# preamp.net
KiCad netlist of a schematic drawn in EAGLE
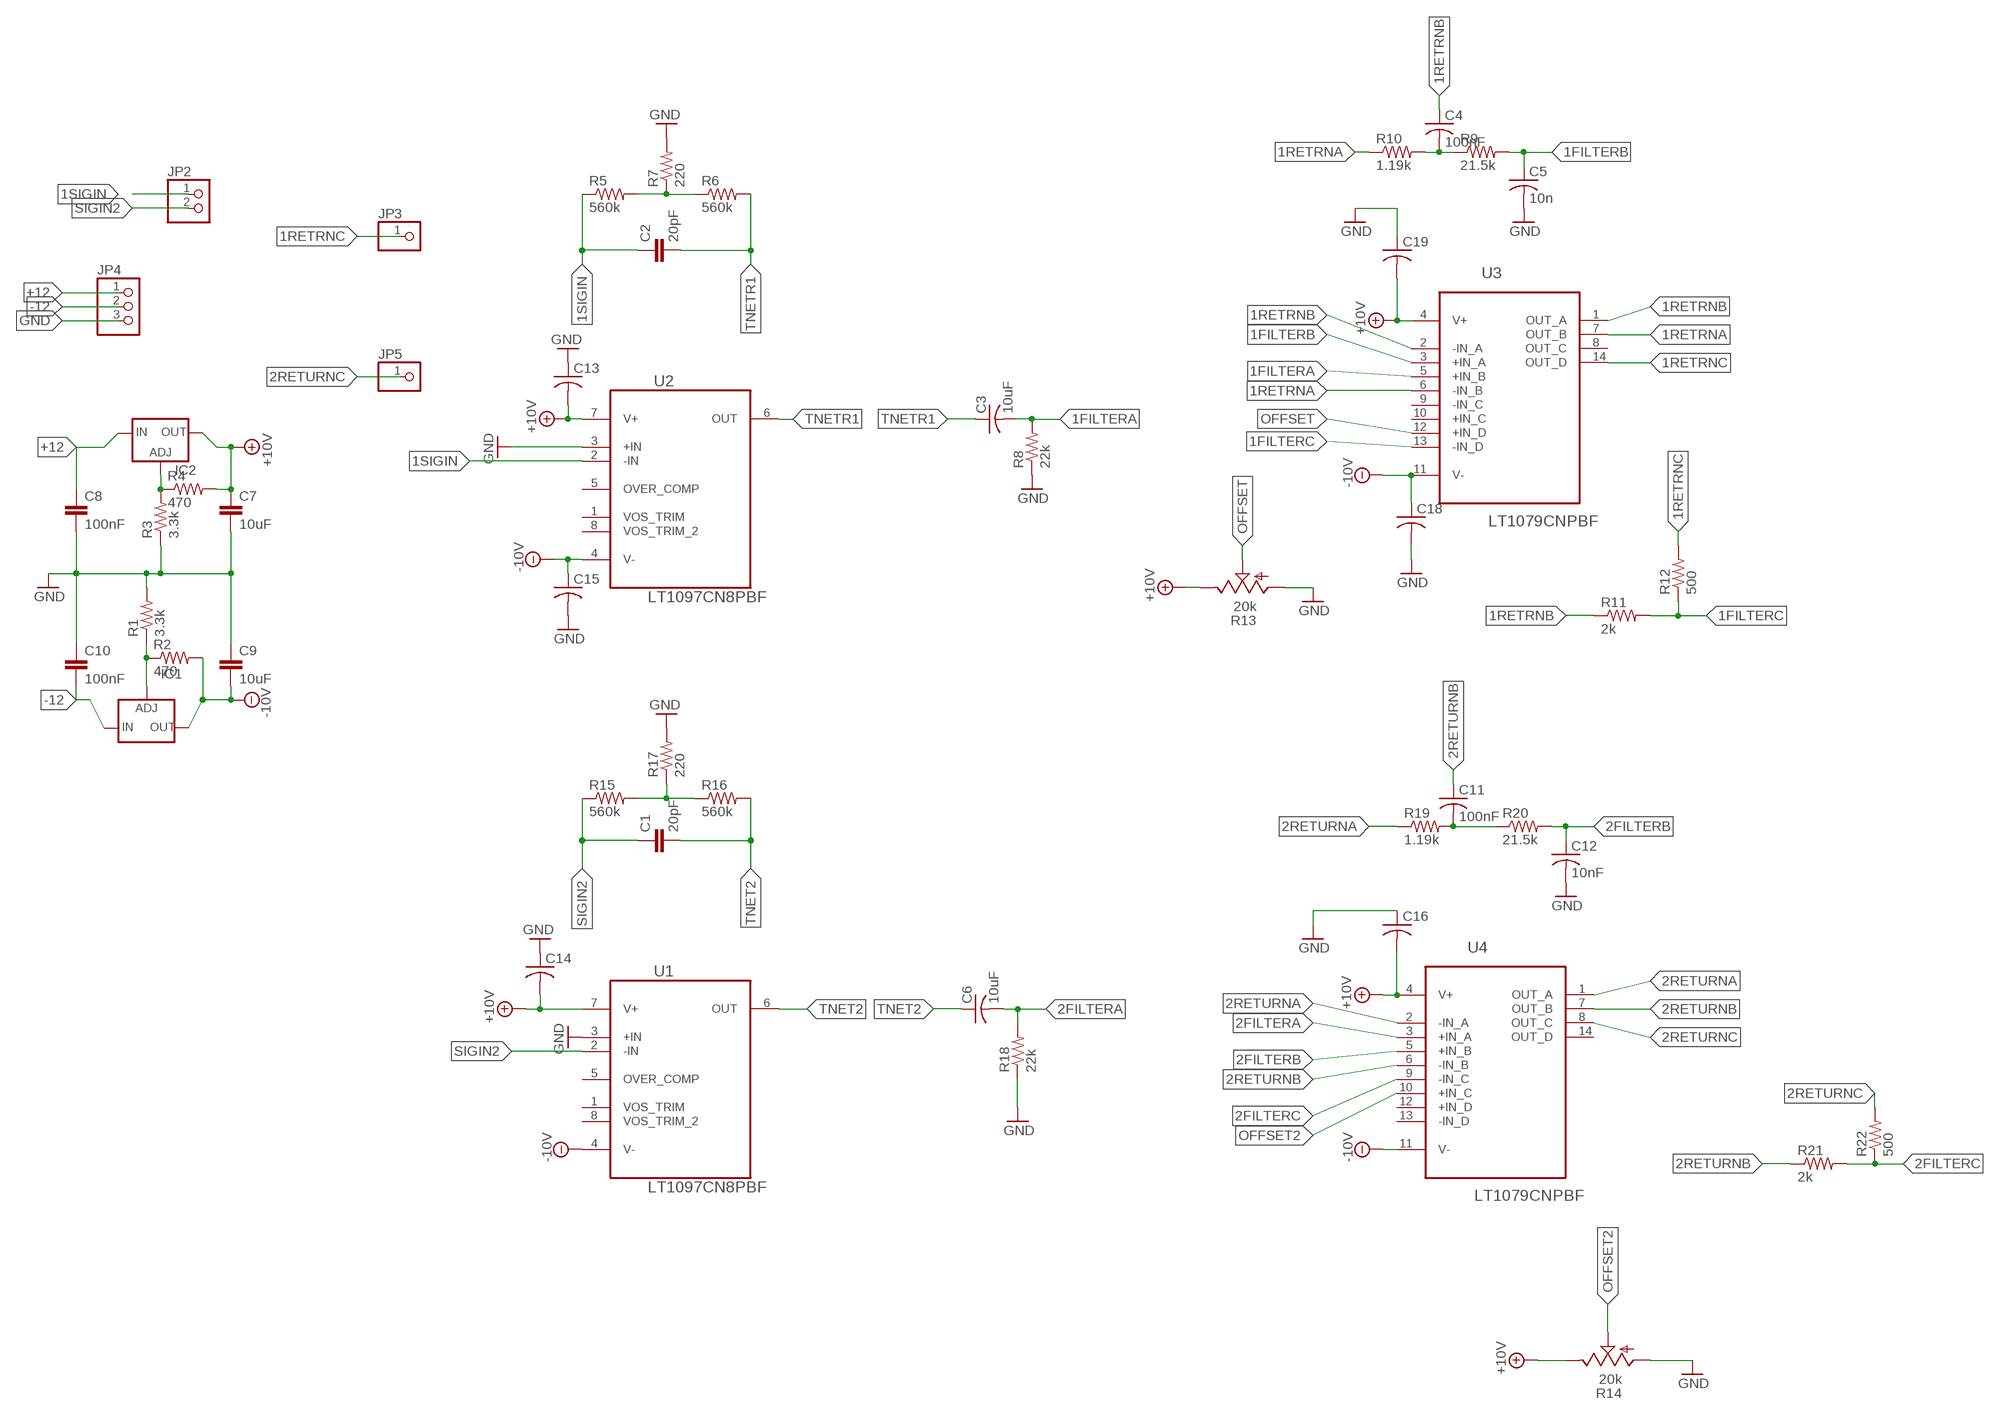
[diagram p0: schematic, sheet 1]

(export (version "E")
  (design (tool "Eeschema 10.0.6"))
  (components
    (comp (ref "C1")
      (value "20pF")
      (footprint "eagle-import:C025-030X050")
      (libsource (lib "eagle-import") (part "C-EU025-030X050"))
    )
    (comp (ref "C2")
      (value "20pF")
      (footprint "eagle-import:C025-030X050")
      (libsource (lib "eagle-import") (part "C-EU025-030X050"))
    )
    (comp (ref "C3")
      (value "10uF")
      (footprint "eagle-import:C050-030X075")
      (libsource (lib "eagle-import") (part "resistor_C-US050-030X075"))
    )
    (comp (ref "C4")
      (value "100nF")
      (footprint "eagle-import:C050-024X044")
      (libsource (lib "eagle-import") (part "resistor_C-US050-024X044"))
    )
    (comp (ref "C5")
      (value "10n")
      (footprint "eagle-import:C025-024X044")
      (libsource (lib "eagle-import") (part "resistor_C-US025-024X044"))
    )
    (comp (ref "C6")
      (value "10uF")
      (footprint "eagle-import:C050-030X075")
      (libsource (lib "eagle-import") (part "resistor_C-US050-030X075"))
    )
    (comp (ref "C7")
      (value "10uF")
      (footprint "eagle-import:C025-025X050")
      (libsource (lib "eagle-import") (part "C-EU025-025X050"))
    )
    (comp (ref "C8")
      (value "100nF")
      (footprint "eagle-import:C025-025X050")
      (libsource (lib "eagle-import") (part "C-EU025-025X050"))
    )
    (comp (ref "C9")
      (value "10uF")
      (footprint "eagle-import:C025-025X050")
      (libsource (lib "eagle-import") (part "C-EU025-025X050"))
    )
    (comp (ref "C10")
      (value "100nF")
      (footprint "eagle-import:C025-025X050")
      (libsource (lib "eagle-import") (part "C-EU025-025X050"))
    )
    (comp (ref "C11")
      (value "100nF")
      (footprint "eagle-import:C050-024X044")
      (libsource (lib "eagle-import") (part "resistor_C-US050-024X044"))
    )
    (comp (ref "C12")
      (value "10nF")
      (footprint "eagle-import:C025-024X044")
      (libsource (lib "eagle-import") (part "resistor_C-US025-024X044"))
    )
    (comp (ref "C13")
      (value "C-US025-024X044")
      (footprint "eagle-import:C025-024X044")
      (libsource (lib "eagle-import") (part "C-US025-024X044"))
    )
    (comp (ref "C14")
      (value "C-US025-024X044")
      (footprint "eagle-import:C025-024X044")
      (libsource (lib "eagle-import") (part "C-US025-024X044"))
    )
    (comp (ref "C15")
      (value "C-US025-024X044")
      (footprint "eagle-import:C025-024X044")
      (libsource (lib "eagle-import") (part "C-US025-024X044"))
    )
    (comp (ref "C16")
      (value "C-US025-024X044")
      (footprint "eagle-import:C025-024X044")
      (libsource (lib "eagle-import") (part "C-US025-024X044"))
    )
    (comp (ref "C18")
      (value "C-US025-024X044")
      (footprint "eagle-import:C025-024X044")
      (libsource (lib "eagle-import") (part "C-US025-024X044"))
    )
    (comp (ref "C19")
      (value "C-US025-024X044")
      (footprint "eagle-import:C025-024X044")
      (libsource (lib "eagle-import") (part "C-US025-024X044"))
    )
    (comp (ref "IC1")
      (value "LM337TS")
      (footprint "eagle-import:337TS")
      (libsource (lib "eagle-import") (part "LM337TS"))
    )
    (comp (ref "IC2")
      (value "LM317TS")
      (footprint "eagle-import:317TS")
      (libsource (lib "eagle-import") (part "LM317TS"))
    )
    (comp (ref "JP2")
      (value "PINHD-1X2")
      (footprint "eagle-import:1X02")
      (libsource (lib "eagle-import") (part "PINHD-1X2"))
    )
    (comp (ref "JP3")
      (value "PINHD-1X1")
      (footprint "eagle-import:1X01")
      (libsource (lib "eagle-import") (part "PINHD-1X1"))
    )
    (comp (ref "JP4")
      (value "PINHD-1X3")
      (footprint "eagle-import:1X03")
      (libsource (lib "eagle-import") (part "PINHD-1X3"))
    )
    (comp (ref "JP5")
      (value "PINHD-1X1")
      (footprint "eagle-import:1X01")
      (libsource (lib "eagle-import") (part "PINHD-1X1"))
    )
    (comp (ref "R1")
      (value "3.3k")
      (footprint "eagle-import:0204_5")
      (libsource (lib "eagle-import") (part "R-US_0204/5"))
    )
    (comp (ref "R2")
      (value "470")
      (footprint "eagle-import:0204_5")
      (libsource (lib "eagle-import") (part "R-US_0204/5"))
    )
    (comp (ref "R3")
      (value "3.3k")
      (footprint "eagle-import:0204_5")
      (libsource (lib "eagle-import") (part "R-US_0204/5"))
    )
    (comp (ref "R4")
      (value "470")
      (footprint "eagle-import:0204_5")
      (libsource (lib "eagle-import") (part "R-US_0204/5"))
    )
    (comp (ref "R5")
      (value "560k")
      (footprint "eagle-import:0204_7")
      (libsource (lib "eagle-import") (part "R-US_0204/7"))
    )
    (comp (ref "R6")
      (value "560k")
      (footprint "eagle-import:0204_7")
      (libsource (lib "eagle-import") (part "R-US_0204/7"))
    )
    (comp (ref "R7")
      (value "220")
      (footprint "eagle-import:0204_7")
      (libsource (lib "eagle-import") (part "R-US_0204/7"))
    )
    (comp (ref "R8")
      (value "22k")
      (footprint "eagle-import:0204_5")
      (libsource (lib "eagle-import") (part "R-US_0204/5"))
    )
    (comp (ref "R9")
      (value "21.5k")
      (footprint "eagle-import:0204_5")
      (libsource (lib "eagle-import") (part "R-US_0204/5"))
    )
    (comp (ref "R10")
      (value "1.19k")
      (footprint "eagle-import:0204_5")
      (libsource (lib "eagle-import") (part "R-US_0204/5"))
    )
    (comp (ref "R11")
      (value "2k")
      (footprint "eagle-import:0204_5")
      (libsource (lib "eagle-import") (part "R-US_0204/5"))
    )
    (comp (ref "R12")
      (value "500")
      (footprint "eagle-import:0204_5")
      (libsource (lib "eagle-import") (part "R-US_0204/5"))
    )
    (comp (ref "R13")
      (value "20k")
      (footprint "eagle-import:B64W")
      (libsource (lib "eagle-import") (part "TRIM_US-B64W"))
    )
    (comp (ref "R14")
      (value "20k")
      (footprint "eagle-import:B64W")
      (libsource (lib "eagle-import") (part "TRIM_US-B64W"))
    )
    (comp (ref "R15")
      (value "560k")
      (footprint "eagle-import:0204_7")
      (libsource (lib "eagle-import") (part "R-US_0204/7"))
    )
    (comp (ref "R16")
      (value "560k")
      (footprint "eagle-import:0204_7")
      (libsource (lib "eagle-import") (part "R-US_0204/7"))
    )
    (comp (ref "R17")
      (value "220")
      (footprint "eagle-import:0204_7")
      (libsource (lib "eagle-import") (part "R-US_0204/7"))
    )
    (comp (ref "R18")
      (value "22k")
      (footprint "eagle-import:0204_5")
      (libsource (lib "eagle-import") (part "R-US_0204/5"))
    )
    (comp (ref "R19")
      (value "1.19k")
      (footprint "eagle-import:0204_5")
      (libsource (lib "eagle-import") (part "R-US_0204/5"))
    )
    (comp (ref "R20")
      (value "21.5k")
      (footprint "eagle-import:0204_5")
      (libsource (lib "eagle-import") (part "R-US_0204/5"))
    )
    (comp (ref "R21")
      (value "2k")
      (footprint "eagle-import:0204_5")
      (libsource (lib "eagle-import") (part "R-US_0204/5"))
    )
    (comp (ref "R22")
      (value "500")
      (footprint "eagle-import:0204_5")
      (libsource (lib "eagle-import") (part "R-US_0204/5"))
    )
    (comp (ref "U1")
      (value "LT1097CN8PBF")
      (footprint "eagle-import:DIP254P762X393-8")
      (fields (field (name "MPN") "LT1097CN8#PBF"))
      (libsource (lib "eagle-import") (part "LT1097CN8PBF"))
    )
    (comp (ref "U2")
      (value "LT1097CN8PBF")
      (footprint "eagle-import:DIP254P762X393-8")
      (fields (field (name "MPN") "LT1097CN8#PBF"))
      (libsource (lib "eagle-import") (part "LT1097CN8PBF"))
    )
    (comp (ref "U3")
      (value "LT1079CNPBF")
      (footprint "eagle-import:DIP254P762X394-14")
      (fields (field (name "MPN") "LT1079CN#PBF"))
      (libsource (lib "eagle-import") (part "LT1079CNPBF"))
    )
    (comp (ref "U4")
      (value "LT1079CNPBF")
      (footprint "eagle-import:DIP254P762X394-14")
      (fields (field (name "MPN") "LT1079CN#PBF"))
      (libsource (lib "eagle-import") (part "LT1079CNPBF"))
    )
  )
  (nets
    (net (code "1") (name "+10V") (class "Default")
      (node (ref "C13") (pin "2") (pinfunction "2_2") (pintype "passive"))
      (node (ref "C14") (pin "2") (pinfunction "2_2") (pintype "passive"))
      (node (ref "C16") (pin "2") (pinfunction "2_2") (pintype "passive"))
      (node (ref "C19") (pin "2") (pinfunction "2_2") (pintype "passive"))
      (node (ref "C7") (pin "1") (pinfunction "1_1") (pintype "passive"))
      (node (ref "IC2") (pin "2") (pinfunction "OUT_2") (pintype "passive"))
      (node (ref "R13") (pin "E") (pinfunction "E_E") (pintype "passive"))
      (node (ref "R14") (pin "E") (pinfunction "E_E") (pintype "passive"))
      (node (ref "R4") (pin "2") (pinfunction "2_2") (pintype "passive"))
      (node (ref "U1") (pin "7") (pinfunction "V+_7") (pintype "power_in"))
      (node (ref "U2") (pin "7") (pinfunction "V+_7") (pintype "power_in"))
      (node (ref "U3") (pin "4") (pinfunction "V+_4") (pintype "power_in"))
      (node (ref "U4") (pin "4") (pinfunction "V+_4") (pintype "power_in"))
    )
    (net (code "2") (name "+12") (class "Default")
      (node (ref "C8") (pin "1") (pinfunction "1_1") (pintype "passive"))
      (node (ref "IC2") (pin "3") (pinfunction "IN_3") (pintype "input"))
      (node (ref "JP4") (pin "1") (pinfunction "1_1") (pintype "passive"))
    )
    (net (code "3") (name "-10V") (class "Default")
      (node (ref "C15") (pin "1") (pinfunction "1_1") (pintype "passive"))
      (node (ref "C18") (pin "1") (pinfunction "1_1") (pintype "passive"))
      (node (ref "C9") (pin "2") (pinfunction "2_2") (pintype "passive"))
      (node (ref "IC1") (pin "3") (pinfunction "OUT_3") (pintype "passive"))
      (node (ref "R2") (pin "2") (pinfunction "2_2") (pintype "passive"))
      (node (ref "U1") (pin "4") (pinfunction "V-_4") (pintype "power_in"))
      (node (ref "U2") (pin "4") (pinfunction "V-_4") (pintype "power_in"))
      (node (ref "U3") (pin "11") (pinfunction "V-_11") (pintype "power_in"))
      (node (ref "U4") (pin "11") (pinfunction "V-_11") (pintype "power_in"))
    )
    (net (code "4") (name "-12") (class "Default")
      (node (ref "C10") (pin "2") (pinfunction "2_2") (pintype "passive"))
      (node (ref "IC1") (pin "2") (pinfunction "IN_2") (pintype "input"))
      (node (ref "JP4") (pin "2") (pinfunction "2_2") (pintype "passive"))
    )
    (net (code "5") (name "1FILTERA") (class "Default")
      (node (ref "C3") (pin "2") (pinfunction "2_2") (pintype "passive"))
      (node (ref "R8") (pin "2") (pinfunction "2_2") (pintype "passive"))
      (node (ref "U3") (pin "5") (pinfunction "+IN_B_5") (pintype "input"))
    )
    (net (code "6") (name "1FILTERB") (class "Default")
      (node (ref "C5") (pin "1") (pinfunction "1_1") (pintype "passive"))
      (node (ref "R9") (pin "2") (pinfunction "2_2") (pintype "passive"))
      (node (ref "U3") (pin "3") (pinfunction "+IN_A_3") (pintype "input"))
    )
    (net (code "7") (name "1FILTERC") (class "Default")
      (node (ref "R11") (pin "2") (pinfunction "2_2") (pintype "passive"))
      (node (ref "R12") (pin "1") (pinfunction "1_1") (pintype "passive"))
      (node (ref "U3") (pin "13") (pinfunction "-IN_D_13") (pintype "input"))
    )
    (net (code "8") (name "1RETRNA") (class "Default")
      (node (ref "R10") (pin "1") (pinfunction "1_1") (pintype "passive"))
      (node (ref "U3") (pin "6") (pinfunction "-IN_B_6") (pintype "input"))
      (node (ref "U3") (pin "7") (pinfunction "OUT_B_7") (pintype "output"))
    )
    (net (code "9") (name "1RETRNB") (class "Default")
      (node (ref "C4") (pin "1") (pinfunction "1_1") (pintype "passive"))
      (node (ref "R11") (pin "1") (pinfunction "1_1") (pintype "passive"))
      (node (ref "U3") (pin "1") (pinfunction "OUT_A_1") (pintype "output"))
      (node (ref "U3") (pin "2") (pinfunction "-IN_A_2") (pintype "input"))
    )
    (net (code "10") (name "1RETRNC") (class "Default")
      (node (ref "JP3") (pin "1") (pinfunction "1_1") (pintype "passive"))
      (node (ref "R12") (pin "2") (pinfunction "2_2") (pintype "passive"))
      (node (ref "U3") (pin "14") (pinfunction "OUT_D_14") (pintype "output"))
    )
    (net (code "11") (name "1SIGIN") (class "Default")
      (node (ref "C2") (pin "1") (pinfunction "1_1") (pintype "passive"))
      (node (ref "JP2") (pin "1") (pinfunction "1_1") (pintype "passive"))
      (node (ref "R5") (pin "1") (pinfunction "1_1") (pintype "passive"))
      (node (ref "U2") (pin "2") (pinfunction "-IN_2") (pintype "input"))
    )
    (net (code "12") (name "2FILTERA") (class "Default")
      (node (ref "C6") (pin "2") (pinfunction "2_2") (pintype "passive"))
      (node (ref "R18") (pin "2") (pinfunction "2_2") (pintype "passive"))
      (node (ref "U4") (pin "3") (pinfunction "+IN_A_3") (pintype "input"))
    )
    (net (code "13") (name "2FILTERB") (class "Default")
      (node (ref "C12") (pin "1") (pinfunction "1_1") (pintype "passive"))
      (node (ref "R20") (pin "2") (pinfunction "2_2") (pintype "passive"))
      (node (ref "U4") (pin "5") (pinfunction "+IN_B_5") (pintype "input"))
    )
    (net (code "14") (name "2FILTERC") (class "Default")
      (node (ref "R21") (pin "2") (pinfunction "2_2") (pintype "passive"))
      (node (ref "R22") (pin "1") (pinfunction "1_1") (pintype "passive"))
      (node (ref "U4") (pin "9") (pinfunction "-IN_C_9") (pintype "input"))
    )
    (net (code "15") (name "2RETURNA") (class "Default")
      (node (ref "R19") (pin "1") (pinfunction "1_1") (pintype "passive"))
      (node (ref "U4") (pin "1") (pinfunction "OUT_A_1") (pintype "output"))
      (node (ref "U4") (pin "2") (pinfunction "-IN_A_2") (pintype "input"))
    )
    (net (code "16") (name "2RETURNB") (class "Default")
      (node (ref "C11") (pin "1") (pinfunction "1_1") (pintype "passive"))
      (node (ref "R21") (pin "1") (pinfunction "1_1") (pintype "passive"))
      (node (ref "U4") (pin "6") (pinfunction "-IN_B_6") (pintype "input"))
      (node (ref "U4") (pin "7") (pinfunction "OUT_B_7") (pintype "output"))
    )
    (net (code "17") (name "2RETURNC") (class "Default")
      (node (ref "JP5") (pin "1") (pinfunction "1_1") (pintype "passive"))
      (node (ref "R22") (pin "2") (pinfunction "2_2") (pintype "passive"))
      (node (ref "U4") (pin "8") (pinfunction "OUT_C_8") (pintype "output"))
    )
    (net (code "18") (name "GND") (class "Default")
      (node (ref "C10") (pin "1") (pinfunction "1_1") (pintype "passive"))
      (node (ref "C12") (pin "2") (pinfunction "2_2") (pintype "passive"))
      (node (ref "C13") (pin "1") (pinfunction "1_1") (pintype "passive"))
      (node (ref "C14") (pin "1") (pinfunction "1_1") (pintype "passive"))
      (node (ref "C15") (pin "2") (pinfunction "2_2") (pintype "passive"))
      (node (ref "C16") (pin "1") (pinfunction "1_1") (pintype "passive"))
      (node (ref "C18") (pin "2") (pinfunction "2_2") (pintype "passive"))
      (node (ref "C19") (pin "1") (pinfunction "1_1") (pintype "passive"))
      (node (ref "C5") (pin "2") (pinfunction "2_2") (pintype "passive"))
      (node (ref "C7") (pin "2") (pinfunction "2_2") (pintype "passive"))
      (node (ref "C8") (pin "2") (pinfunction "2_2") (pintype "passive"))
      (node (ref "C9") (pin "1") (pinfunction "1_1") (pintype "passive"))
      (node (ref "JP4") (pin "3") (pinfunction "3_3") (pintype "passive"))
      (node (ref "R1") (pin "2") (pinfunction "2_2") (pintype "passive"))
      (node (ref "R13") (pin "A") (pinfunction "A_A") (pintype "passive"))
      (node (ref "R14") (pin "A") (pinfunction "A_A") (pintype "passive"))
      (node (ref "R17") (pin "2") (pinfunction "2_2") (pintype "passive"))
      (node (ref "R18") (pin "1") (pinfunction "1_1") (pintype "passive"))
      (node (ref "R3") (pin "1") (pinfunction "1_1") (pintype "passive"))
      (node (ref "R7") (pin "2") (pinfunction "2_2") (pintype "passive"))
      (node (ref "R8") (pin "1") (pinfunction "1_1") (pintype "passive"))
      (node (ref "U1") (pin "3") (pinfunction "+IN_3") (pintype "input"))
      (node (ref "U2") (pin "3") (pinfunction "+IN_3") (pintype "input"))
    )
    (net (code "19") (name "Net-(C4-Pad2)") (class "Default")
      (node (ref "C4") (pin "2") (pinfunction "2_2") (pintype "passive"))
      (node (ref "R10") (pin "2") (pinfunction "2_2") (pintype "passive"))
      (node (ref "R9") (pin "1") (pinfunction "1_1") (pintype "passive"))
    )
    (net (code "20") (name "Net-(C11-Pad2)") (class "Default")
      (node (ref "C11") (pin "2") (pinfunction "2_2") (pintype "passive"))
      (node (ref "R19") (pin "2") (pinfunction "2_2") (pintype "passive"))
      (node (ref "R20") (pin "1") (pinfunction "1_1") (pintype "passive"))
    )
    (net (code "21") (name "Net-(IC1-ADJ)") (class "Default")
      (node (ref "IC1") (pin "1") (pinfunction "ADJ_1") (pintype "input"))
      (node (ref "R1") (pin "1") (pinfunction "1_1") (pintype "passive"))
      (node (ref "R2") (pin "1") (pinfunction "1_1") (pintype "passive"))
    )
    (net (code "22") (name "Net-(IC2-ADJ)") (class "Default")
      (node (ref "IC2") (pin "1") (pinfunction "ADJ_1") (pintype "input"))
      (node (ref "R3") (pin "2") (pinfunction "2_2") (pintype "passive"))
      (node (ref "R4") (pin "1") (pinfunction "1_1") (pintype "passive"))
    )
    (net (code "23") (name "Net-(R5-Pad2)") (class "Default")
      (node (ref "R5") (pin "2") (pinfunction "2_2") (pintype "passive"))
      (node (ref "R6") (pin "1") (pinfunction "1_1") (pintype "passive"))
      (node (ref "R7") (pin "1") (pinfunction "1_1") (pintype "passive"))
    )
    (net (code "24") (name "Net-(R15-Pad2)") (class "Default")
      (node (ref "R15") (pin "2") (pinfunction "2_2") (pintype "passive"))
      (node (ref "R16") (pin "1") (pinfunction "1_1") (pintype "passive"))
      (node (ref "R17") (pin "1") (pinfunction "1_1") (pintype "passive"))
    )
    (net (code "25") (name "OFFSET") (class "Default")
      (node (ref "R13") (pin "S") (pinfunction "S_S") (pintype "passive"))
      (node (ref "U3") (pin "12") (pinfunction "+IN_D_12") (pintype "input"))
    )
    (net (code "26") (name "OFFSET2") (class "Default")
      (node (ref "R14") (pin "S") (pinfunction "S_S") (pintype "passive"))
      (node (ref "U4") (pin "10") (pinfunction "+IN_C_10") (pintype "input"))
    )
    (net (code "27") (name "SIGIN2") (class "Default")
      (node (ref "C1") (pin "1") (pinfunction "1_1") (pintype "passive"))
      (node (ref "JP2") (pin "2") (pinfunction "2_2") (pintype "passive"))
      (node (ref "R15") (pin "1") (pinfunction "1_1") (pintype "passive"))
      (node (ref "U1") (pin "2") (pinfunction "-IN_2") (pintype "input"))
    )
    (net (code "28") (name "TNET2") (class "Default")
      (node (ref "C1") (pin "2") (pinfunction "2_2") (pintype "passive"))
      (node (ref "C6") (pin "1") (pinfunction "1_1") (pintype "passive"))
      (node (ref "R16") (pin "2") (pinfunction "2_2") (pintype "passive"))
      (node (ref "U1") (pin "6") (pinfunction "OUT_6") (pintype "output"))
    )
    (net (code "29") (name "TNETR1") (class "Default")
      (node (ref "C2") (pin "2") (pinfunction "2_2") (pintype "passive"))
      (node (ref "C3") (pin "1") (pinfunction "1_1") (pintype "passive"))
      (node (ref "R6") (pin "2") (pinfunction "2_2") (pintype "passive"))
      (node (ref "U2") (pin "6") (pinfunction "OUT_6") (pintype "output"))
    )
    (net (code "30") (name "unconnected-(U1-OVER_COMP-Pad5)") (class "Default")
      (node (ref "U1") (pin "5") (pinfunction "OVER_COMP_5") (pintype "passive"))
    )
    (net (code "31") (name "unconnected-(U1-VOS_TRIM-Pad1)") (class "Default")
      (node (ref "U1") (pin "1") (pinfunction "VOS_TRIM_1") (pintype "passive"))
    )
    (net (code "32") (name "unconnected-(U1-VOS_TRIM_2-Pad8)") (class "Default")
      (node (ref "U1") (pin "8") (pinfunction "VOS_TRIM_2_8") (pintype "passive"))
    )
    (net (code "33") (name "unconnected-(U2-OVER_COMP-Pad5)") (class "Default")
      (node (ref "U2") (pin "5") (pinfunction "OVER_COMP_5") (pintype "passive"))
    )
    (net (code "34") (name "unconnected-(U2-VOS_TRIM-Pad1)") (class "Default")
      (node (ref "U2") (pin "1") (pinfunction "VOS_TRIM_1") (pintype "passive"))
    )
    (net (code "35") (name "unconnected-(U2-VOS_TRIM_2-Pad8)") (class "Default")
      (node (ref "U2") (pin "8") (pinfunction "VOS_TRIM_2_8") (pintype "passive"))
    )
    (net (code "36") (name "unconnected-(U3-+IN_C-Pad10)") (class "Default")
      (node (ref "U3") (pin "10") (pinfunction "+IN_C_10") (pintype "input"))
    )
    (net (code "37") (name "unconnected-(U3--IN_C-Pad9)") (class "Default")
      (node (ref "U3") (pin "9") (pinfunction "-IN_C_9") (pintype "input"))
    )
    (net (code "38") (name "unconnected-(U3-OUT_C-Pad8)") (class "Default")
      (node (ref "U3") (pin "8") (pinfunction "OUT_C_8") (pintype "output"))
    )
    (net (code "39") (name "unconnected-(U4-+IN_D-Pad12)") (class "Default")
      (node (ref "U4") (pin "12") (pinfunction "+IN_D_12") (pintype "input"))
    )
    (net (code "40") (name "unconnected-(U4--IN_D-Pad13)") (class "Default")
      (node (ref "U4") (pin "13") (pinfunction "-IN_D_13") (pintype "input"))
    )
    (net (code "41") (name "unconnected-(U4-OUT_D-Pad14)") (class "Default")
      (node (ref "U4") (pin "14") (pinfunction "OUT_D_14") (pintype "output"))
    )
  )
)
